# Schematic.net
KiCad netlist of a schematic drawn in EAGLE
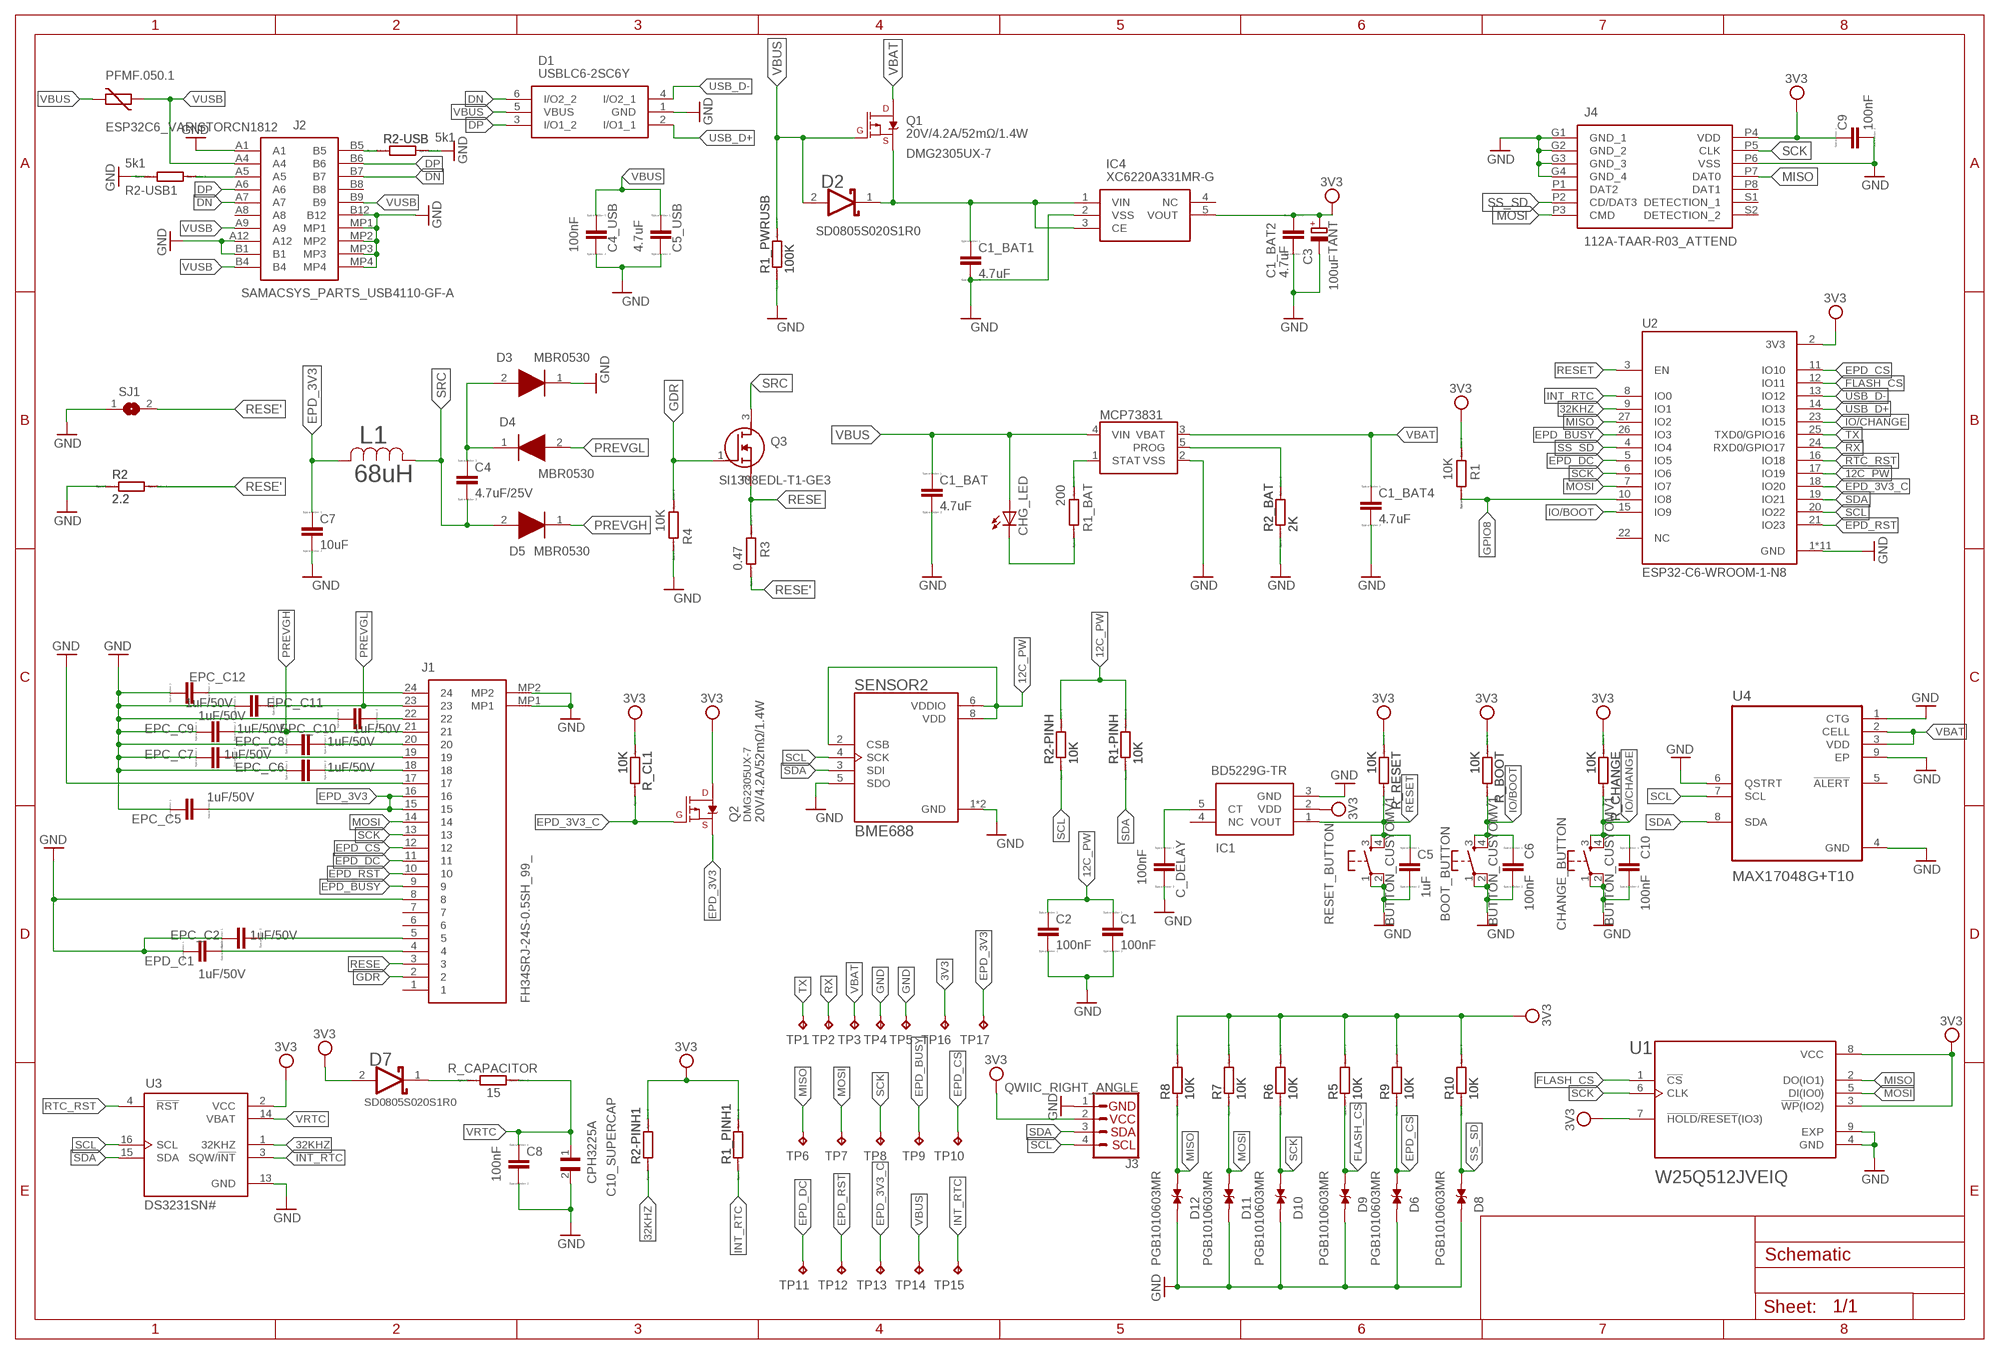
[diagram p0: schematic, sheet 1]

(export (version "E")
  (design (tool "Eeschema 10.0.6"))
  (components
    (comp (ref "BOOT_BUTTON")
      (value "BUTTON_CUSYOMV1")
      (footprint "eagle-import:MYBUTTON")
      (libsource (lib "eagle-import") (part "BUTTON_CUSYOMV1"))
    )
    (comp (ref "C1")
      (value "100nF")
      (footprint "eagle-import:EAGLE-LTSPICE_C0402")
      (libsource (lib "eagle-import") (part "EAGLE-LTSPICE_CC0402"))
    )
    (comp (ref "C1_BAT")
      (value "4.7uF")
      (footprint "eagle-import:EAGLE-LTSPICE_C0402")
      (libsource (lib "eagle-import") (part "EAGLE-LTSPICE_CC0402"))
    )
    (comp (ref "C1_BAT1")
      (value "4.7uF")
      (footprint "eagle-import:EAGLE-LTSPICE_C0402")
      (libsource (lib "eagle-import") (part "EAGLE-LTSPICE_CC0402"))
    )
    (comp (ref "C1_BAT2")
      (value "4.7uF")
      (footprint "eagle-import:EAGLE-LTSPICE_C0402")
      (libsource (lib "eagle-import") (part "EAGLE-LTSPICE_CC0402"))
    )
    (comp (ref "C1_BAT4")
      (value "4.7uF")
      (footprint "eagle-import:EAGLE-LTSPICE_C0402")
      (libsource (lib "eagle-import") (part "EAGLE-LTSPICE_CC0402"))
    )
    (comp (ref "C2")
      (value "100nF")
      (footprint "eagle-import:EAGLE-LTSPICE_C0402")
      (libsource (lib "eagle-import") (part "EAGLE-LTSPICE_CC0402"))
    )
    (comp (ref "C3")
      (value "100uF")
      (footprint "eagle-import:RCL_CT3528")
      (libsource (lib "eagle-import") (part "RCL_CPOL-EUCT3528"))
    )
    (comp (ref "C4")
      (value "4.7uF/25V")
      (footprint "eagle-import:EAGLE-LTSPICE_C0402")
      (libsource (lib "eagle-import") (part "EAGLE-LTSPICE_CC0402"))
    )
    (comp (ref "C4_USB")
      (value "100nF")
      (footprint "eagle-import:EAGLE-LTSPICE_C0402")
      (libsource (lib "eagle-import") (part "EAGLE-LTSPICE_CC0402"))
    )
    (comp (ref "C5")
      (value "1uF")
      (footprint "eagle-import:EAGLE-LTSPICE_C0402")
      (libsource (lib "eagle-import") (part "EAGLE-LTSPICE_CC0402"))
    )
    (comp (ref "C5_USB")
      (value "4.7uF")
      (footprint "eagle-import:EAGLE-LTSPICE_C0402")
      (libsource (lib "eagle-import") (part "EAGLE-LTSPICE_CC0402"))
    )
    (comp (ref "C6")
      (value "100nF")
      (footprint "eagle-import:EAGLE-LTSPICE_C0402")
      (libsource (lib "eagle-import") (part "EAGLE-LTSPICE_CC0402"))
    )
    (comp (ref "C7")
      (value "10uF")
      (footprint "eagle-import:EAGLE-LTSPICE_C0402")
      (libsource (lib "eagle-import") (part "EAGLE-LTSPICE_CC0402"))
    )
    (comp (ref "C8")
      (value "100nF")
      (footprint "eagle-import:EAGLE-LTSPICE_C0402")
      (libsource (lib "eagle-import") (part "EAGLE-LTSPICE_CC0402"))
    )
    (comp (ref "C9")
      (value "100nF")
      (footprint "eagle-import:EAGLE-LTSPICE_C0402")
      (libsource (lib "eagle-import") (part "EAGLE-LTSPICE_CC0402"))
    )
    (comp (ref "C10")
      (value "100nF")
      (footprint "eagle-import:EAGLE-LTSPICE_C0402")
      (libsource (lib "eagle-import") (part "EAGLE-LTSPICE_CC0402"))
    )
    (comp (ref "C10_SUPERCAP")
      (value "CPH3225A")
      (footprint "eagle-import:CAPCP3225X100N")
      (fields (field (name "MF") "Seiko Instruments"))
      (libsource (lib "eagle-import") (part "CPH3225A"))
    )
    (comp (ref "CHANGE_BUTTON")
      (value "BUTTON_CUSYOMV1")
      (footprint "eagle-import:MYBUTTON")
      (libsource (lib "eagle-import") (part "BUTTON_CUSYOMV1"))
    )
    (comp (ref "CHG_LED")
      (value "ADAFRUIT_LEDCHIP-LED0603")
      (footprint "eagle-import:ADAFRUIT_CHIP-LED0603")
      (libsource (lib "eagle-import") (part "ADAFRUIT_LEDCHIP-LED0603"))
    )
    (comp (ref "C_DELAY")
      (value "100nF")
      (footprint "eagle-import:EAGLE-LTSPICE_C0402")
      (libsource (lib "eagle-import") (part "EAGLE-LTSPICE_CC0402"))
    )
    (comp (ref "D1")
      (value "USBLC6-2SC6Y")
      (footprint "eagle-import:SOT95P280X145-6N")
      (fields (field (name "MF") "STMicroelectronics"))
      (libsource (lib "eagle-import") (part "USBLC6-2SC6Y"))
    )
    (comp (ref "D2")
      (value "ESP32_WROVER_AVX---SD0805S020S1R0_AVX_SD0805S020S1R0_0_0AVX_SD0805S020S1R0_0_0")
      (footprint "eagle-import:ESP32_WROVER_AVX---SD0805S020S1R0_AVX_SD0805S020S1R0_0")
      (fields
        (field (name "DIGIKEY_PART_NUMBER") "478-7800-1-ND")
        (field (name "MF") "AVX")
        (field (name "MOUSER_PART_NUMBER") "581-SD0805S020S1R0")
      )
      (libsource (lib "eagle-import") (part "ESP32_WROVER_AVX---SD0805S020S1R0_AVX_SD0805S020S1R0_0_0AVX_SD0805S020S1R0_0_0"))
    )
    (comp (ref "D3")
      (value "MBR0530")
      (footprint "eagle-import:SOD3716X135N")
      (fields (field (name "MF") "ON Semiconductor"))
      (libsource (lib "eagle-import") (part "MBR0530"))
    )
    (comp (ref "D4")
      (value "MBR0530")
      (footprint "eagle-import:SOD3716X135N")
      (fields (field (name "MF") "ON Semiconductor"))
      (libsource (lib "eagle-import") (part "MBR0530"))
    )
    (comp (ref "D5")
      (value "MBR0530")
      (footprint "eagle-import:SOD3716X135N")
      (fields (field (name "MF") "ON Semiconductor"))
      (libsource (lib "eagle-import") (part "MBR0530"))
    )
    (comp (ref "D6")
      (value "PGB1010603MR")
      (footprint "eagle-import:DIOC1608X36N")
      (fields (field (name "MF") "Littelfuse Inc."))
      (libsource (lib "eagle-import") (part "PGB1010603MR"))
    )
    (comp (ref "D7")
      (value "SD0805S020S1R0")
      (footprint "eagle-import:ESP32_WROVER_AVX---SD0805S020S1R0_AVX_SD0805S020S1R0_0")
      (fields
        (field (name "DIGIKEY_PART_NUMBER") "478-7800-1-ND")
        (field (name "MF") "AVX")
        (field (name "MOUSER_PART_NUMBER") "581-SD0805S020S1R0")
      )
      (libsource (lib "eagle-import") (part "ESP32_WROVER_AVX---SD0805S020S1R0_AVX_SD0805S020S1R0_0_0AVX_SD0805S020S1R0_0_0"))
    )
    (comp (ref "D8")
      (value "PGB1010603MR")
      (footprint "eagle-import:DIOC1608X36N")
      (fields (field (name "MF") "Littelfuse Inc."))
      (libsource (lib "eagle-import") (part "PGB1010603MR"))
    )
    (comp (ref "D9")
      (value "PGB1010603MR")
      (footprint "eagle-import:DIOC1608X36N")
      (fields (field (name "MF") "Littelfuse Inc."))
      (libsource (lib "eagle-import") (part "PGB1010603MR"))
    )
    (comp (ref "D10")
      (value "PGB1010603MR")
      (footprint "eagle-import:DIOC1608X36N")
      (fields (field (name "MF") "Littelfuse Inc."))
      (libsource (lib "eagle-import") (part "PGB1010603MR"))
    )
    (comp (ref "D11")
      (value "PGB1010603MR")
      (footprint "eagle-import:DIOC1608X36N")
      (fields (field (name "MF") "Littelfuse Inc."))
      (libsource (lib "eagle-import") (part "PGB1010603MR"))
    )
    (comp (ref "D12")
      (value "PGB1010603MR")
      (footprint "eagle-import:DIOC1608X36N")
      (fields (field (name "MF") "Littelfuse Inc."))
      (libsource (lib "eagle-import") (part "PGB1010603MR"))
    )
    (comp (ref "EPC_C2")
      (value "1uF/50V")
      (footprint "eagle-import:ESP32_WROVER_EAGLE-LTSPICE_C0402")
      (libsource (lib "eagle-import") (part "ESP32_WROVER_EAGLE-LTSPICE_CC0402"))
    )
    (comp (ref "EPC_C5")
      (value "1uF/50V")
      (footprint "eagle-import:ESP32_WROVER_EAGLE-LTSPICE_C0402")
      (libsource (lib "eagle-import") (part "ESP32_WROVER_EAGLE-LTSPICE_CC0402"))
    )
    (comp (ref "EPC_C6")
      (value "1uF/50V")
      (footprint "eagle-import:ESP32_WROVER_EAGLE-LTSPICE_C0402")
      (libsource (lib "eagle-import") (part "ESP32_WROVER_EAGLE-LTSPICE_CC0402"))
    )
    (comp (ref "EPC_C7")
      (value "1uF/50V")
      (footprint "eagle-import:ESP32_WROVER_EAGLE-LTSPICE_C0402")
      (libsource (lib "eagle-import") (part "ESP32_WROVER_EAGLE-LTSPICE_CC0402"))
    )
    (comp (ref "EPC_C8")
      (value "1uF/50V")
      (footprint "eagle-import:ESP32_WROVER_EAGLE-LTSPICE_C0402")
      (libsource (lib "eagle-import") (part "ESP32_WROVER_EAGLE-LTSPICE_CC0402"))
    )
    (comp (ref "EPC_C9")
      (value "1uF/50V")
      (footprint "eagle-import:ESP32_WROVER_EAGLE-LTSPICE_C0402")
      (libsource (lib "eagle-import") (part "ESP32_WROVER_EAGLE-LTSPICE_CC0402"))
    )
    (comp (ref "EPC_C10")
      (value "1uF/50V")
      (footprint "eagle-import:ESP32_WROVER_EAGLE-LTSPICE_C0402")
      (libsource (lib "eagle-import") (part "ESP32_WROVER_EAGLE-LTSPICE_CC0402"))
    )
    (comp (ref "EPC_C11")
      (value "1uF/50V")
      (footprint "eagle-import:ESP32_WROVER_EAGLE-LTSPICE_C0402")
      (libsource (lib "eagle-import") (part "ESP32_WROVER_EAGLE-LTSPICE_CC0402"))
    )
    (comp (ref "EPC_C12")
      (value "1uF/50V")
      (footprint "eagle-import:ESP32_WROVER_EAGLE-LTSPICE_C0402")
      (libsource (lib "eagle-import") (part "ESP32_WROVER_EAGLE-LTSPICE_CC0402"))
    )
    (comp (ref "EPD_C1")
      (value "1uF/50V")
      (footprint "eagle-import:ESP32_WROVER_EAGLE-LTSPICE_C0402")
      (libsource (lib "eagle-import") (part "ESP32_WROVER_EAGLE-LTSPICE_CC0402"))
    )
    (comp (ref "IC1")
      (value "BD5229G-TR")
      (footprint "eagle-import:SOT95P280X125-5N")
      (fields (field (name "MOUSER_PART_NUMBER") "755-BD5229G-TR"))
      (libsource (lib "eagle-import") (part "BD5229G-TR"))
    )
    (comp (ref "IC4")
      (value "XC6220A331MR-G")
      (footprint "eagle-import:SOT95P280X120-5N")
      (fields (field (name "MOUSER_PART_NUMBER") "865-XC6220A331MR-G"))
      (libsource (lib "eagle-import") (part "XC6220A331MR-G"))
    )
    (comp (ref "J1")
      (value "FH34SRJ-24S-0.5SH_99_")
      (footprint "eagle-import:FH34SRJ24S05SH99")
      (fields
        (field (name "MANUFACTURER_PART_NUMBER") "FH34SRJ-24S-0.5SH(99)")
        (field (name "MOUSER_PART_NUMBER") "798-FH34SRJ24S05SH99")
      )
      (libsource (lib "eagle-import") (part "FH34SRJ-24S-0.5SH_99_"))
    )
    (comp (ref "J2")
      (value "SAMACSYS_PARTS_USB4110-GF-A")
      (footprint "eagle-import:SAMACSYS_PARTS_USB4110GFA")
      (fields
        (field (name "MANUFACTURER_PART_NUMBER") "USB4110-GF-A")
        (field (name "MOUSER_PART_NUMBER") "640-USB4110-GF-A")
      )
      (libsource (lib "eagle-import") (part "SAMACSYS_PARTS_USB4110-GF-A"))
    )
    (comp (ref "J3")
      (value "QWIIC_RIGHT_ANGLE")
      (footprint "eagle-import:JST04_1MM_RA")
      (libsource (lib "eagle-import") (part "QWIIC_CONNECTORJS-1MM"))
    )
    (comp (ref "J4")
      (value "112A-TAAR-R03_ATTEND")
      (footprint "eagle-import:112ATAARR03ATTEND")
      (fields (field (name "MANUFACTURER_PART_NUMBER") "112A-TAAR-R03 ATTEND"))
      (libsource (lib "eagle-import") (part "112A-TAAR-R03_ATTEND"))
    )
    (comp (ref "L1")
      (value "68uH")
      (footprint "eagle-import:IND_4828-WE-TPC_WRE")
      (fields
        (field (name "MANUFACTURER_PART_NUMBER") "744043680")
        (field (name "COPYRIGHT") "Copyright (C) 2024 Ultra Librarian. All rights reserved.")
      )
      (libsource (lib "eagle-import") (part "744043680IND_4828-WE-TPC_WRE"))
    )
    (comp (ref "MCP73831")
      (value "ESP32_WROVER_SPARKFUN-IC-POWER_MCP73831")
      (footprint "eagle-import:ESP32_WROVER_SPARKFUN-IC-POWER_SOT23-5")
      (libsource (lib "eagle-import") (part "ESP32_WROVER_SPARKFUN-IC-POWER_MCP73831"))
    )
    (comp (ref "PFMF.050.1")
      (value "ESP32C6_VARISTORCN1812")
      (footprint "eagle-import:ESP32C6_VARISTOR_CT_CN1812")
      (libsource (lib "eagle-import") (part "ESP32C6_VARISTORCN1812"))
    )
    (comp (ref "Q1")
      (value "20V/4.2A/52mΩ/1.4W")
      (footprint "eagle-import:ESP32_WROVER_SPARKFUN-DISCRETESEMI_SOT23-3")
      (libsource (lib "eagle-import") (part "ESP32_WROVER_SPARKFUN-DISCRETESEMI_MOSFET_PCH-DMG2305UX-7"))
    )
    (comp (ref "Q2")
      (value "20V/4.2A/52mΩ/1.4W")
      (footprint "eagle-import:ESP32_WROVER_SPARKFUN-DISCRETESEMI_SOT23-3")
      (libsource (lib "eagle-import") (part "ESP32_WROVER_SPARKFUN-DISCRETESEMI_MOSFET_PCH-DMG2305UX-7"))
    )
    (comp (ref "Q3")
      (value "SI1308EDL-T1-GE3")
      (footprint "eagle-import:SOT65P210X110-3N")
      (fields (field (name "MF") "Vishay Siliconix"))
      (libsource (lib "eagle-import") (part "SI1308EDL-T1-GE3"))
    )
    (comp (ref "R1")
      (value "10K")
      (footprint "eagle-import:ESP32_WROVER_EAGLE-LTSPICE_R0402")
      (libsource (lib "eagle-import") (part "ESP32_WROVER_EAGLE-LTSPICE_RR0402"))
    )
    (comp (ref "R1-PINH")
      (value "10K")
      (footprint "eagle-import:ESP32_WROVER_EAGLE-LTSPICE_R0402")
      (libsource (lib "eagle-import") (part "ESP32_WROVER_EAGLE-LTSPICE_RR0402"))
    )
    (comp (ref "R1_BAT")
      (value "200")
      (footprint "eagle-import:ESP32_WROVER_EAGLE-LTSPICE_R0402")
      (libsource (lib "eagle-import") (part "ESP32_WROVER_EAGLE-LTSPICE_RR0402"))
    )
    (comp (ref "R1_PINH1")
      (value "ESP32_WROVER_EAGLE-LTSPICE_RR0402")
      (footprint "eagle-import:ESP32_WROVER_EAGLE-LTSPICE_R0402")
      (libsource (lib "eagle-import") (part "ESP32_WROVER_EAGLE-LTSPICE_RR0402"))
    )
    (comp (ref "R1_PWRUSB")
      (value "100K")
      (footprint "eagle-import:ESP32_WROVER_EAGLE-LTSPICE_R0402")
      (libsource (lib "eagle-import") (part "ESP32_WROVER_EAGLE-LTSPICE_RR0402"))
    )
    (comp (ref "R2")
      (value "2.2")
      (footprint "eagle-import:ESP32_WROVER_EAGLE-LTSPICE_R0402")
      (libsource (lib "eagle-import") (part "ESP32_WROVER_EAGLE-LTSPICE_RR0402"))
    )
    (comp (ref "R2-PINH")
      (value "10K")
      (footprint "eagle-import:ESP32_WROVER_EAGLE-LTSPICE_R0402")
      (libsource (lib "eagle-import") (part "ESP32_WROVER_EAGLE-LTSPICE_RR0402"))
    )
    (comp (ref "R2-PINH1")
      (value "ESP32_WROVER_EAGLE-LTSPICE_RR0402")
      (footprint "eagle-import:ESP32_WROVER_EAGLE-LTSPICE_R0402")
      (libsource (lib "eagle-import") (part "ESP32_WROVER_EAGLE-LTSPICE_RR0402"))
    )
    (comp (ref "R2-USB")
      (value "5k1")
      (footprint "eagle-import:ESP32_WROVER_EAGLE-LTSPICE_R0402")
      (libsource (lib "eagle-import") (part "ESP32_WROVER_EAGLE-LTSPICE_RR0402"))
    )
    (comp (ref "R2-USB1")
      (value "5k1")
      (footprint "eagle-import:ESP32_WROVER_EAGLE-LTSPICE_R0402")
      (libsource (lib "eagle-import") (part "ESP32_WROVER_EAGLE-LTSPICE_RR0402"))
    )
    (comp (ref "R2_BAT")
      (value "2K")
      (footprint "eagle-import:ESP32_WROVER_EAGLE-LTSPICE_R0402")
      (libsource (lib "eagle-import") (part "ESP32_WROVER_EAGLE-LTSPICE_RR0402"))
    )
    (comp (ref "R3")
      (value "0.47")
      (footprint "eagle-import:ESP32_WROVER_EAGLE-LTSPICE_R0402")
      (libsource (lib "eagle-import") (part "ESP32_WROVER_EAGLE-LTSPICE_RR0402"))
    )
    (comp (ref "R4")
      (value "10K")
      (footprint "eagle-import:ESP32_WROVER_EAGLE-LTSPICE_R0402")
      (libsource (lib "eagle-import") (part "ESP32_WROVER_EAGLE-LTSPICE_RR0402"))
    )
    (comp (ref "R5")
      (value "10K")
      (footprint "eagle-import:ESP32_WROVER_EAGLE-LTSPICE_R0402")
      (libsource (lib "eagle-import") (part "ESP32_WROVER_EAGLE-LTSPICE_RR0402"))
    )
    (comp (ref "R6")
      (value "10K")
      (footprint "eagle-import:ESP32_WROVER_EAGLE-LTSPICE_R0402")
      (libsource (lib "eagle-import") (part "ESP32_WROVER_EAGLE-LTSPICE_RR0402"))
    )
    (comp (ref "R7")
      (value "10K")
      (footprint "eagle-import:ESP32_WROVER_EAGLE-LTSPICE_R0402")
      (libsource (lib "eagle-import") (part "ESP32_WROVER_EAGLE-LTSPICE_RR0402"))
    )
    (comp (ref "R8")
      (value "10K")
      (footprint "eagle-import:ESP32_WROVER_EAGLE-LTSPICE_R0402")
      (libsource (lib "eagle-import") (part "ESP32_WROVER_EAGLE-LTSPICE_RR0402"))
    )
    (comp (ref "R9")
      (value "10K")
      (footprint "eagle-import:ESP32_WROVER_EAGLE-LTSPICE_R0402")
      (libsource (lib "eagle-import") (part "ESP32_WROVER_EAGLE-LTSPICE_RR0402"))
    )
    (comp (ref "R10")
      (value "10K")
      (footprint "eagle-import:ESP32_WROVER_EAGLE-LTSPICE_R0402")
      (libsource (lib "eagle-import") (part "ESP32_WROVER_EAGLE-LTSPICE_RR0402"))
    )
    (comp (ref "RESET_BUTTON")
      (value "BUTTON_CUSYOMV1")
      (footprint "eagle-import:MYBUTTON")
      (libsource (lib "eagle-import") (part "BUTTON_CUSYOMV1"))
    )
    (comp (ref "R_BOOT")
      (value "10K")
      (footprint "eagle-import:ESP32_WROVER_EAGLE-LTSPICE_R0402")
      (libsource (lib "eagle-import") (part "ESP32_WROVER_EAGLE-LTSPICE_RR0402"))
    )
    (comp (ref "R_CAPACITOR")
      (value "15")
      (footprint "eagle-import:ESP32_WROVER_EAGLE-LTSPICE_R0402")
      (libsource (lib "eagle-import") (part "ESP32_WROVER_EAGLE-LTSPICE_RR0402"))
    )
    (comp (ref "R_CHANGE")
      (value "10K")
      (footprint "eagle-import:ESP32_WROVER_EAGLE-LTSPICE_R0402")
      (libsource (lib "eagle-import") (part "ESP32_WROVER_EAGLE-LTSPICE_RR0402"))
    )
    (comp (ref "R_CL1")
      (value "10K")
      (footprint "eagle-import:ESP32_WROVER_EAGLE-LTSPICE_R0402")
      (libsource (lib "eagle-import") (part "ESP32_WROVER_EAGLE-LTSPICE_RR0402"))
    )
    (comp (ref "R_RESET")
      (value "10K")
      (footprint "eagle-import:ESP32_WROVER_EAGLE-LTSPICE_R0402")
      (libsource (lib "eagle-import") (part "ESP32_WROVER_EAGLE-LTSPICE_RR0402"))
    )
    (comp (ref "SENSOR2")
      (value "BME688")
      (footprint "eagle-import:ESP32_WROVER_BME680_PSON80P300X300X100-8N")
      (fields (field (name "MF") "Bosch Sensortec") (field (name "MP") "BME680"))
      (libsource (lib "eagle-import") (part "ESP32_WROVER_BME680_BME680"))
    )
    (comp (ref "SJ1") (value "SJ") (footprint "eagle-import:SJ") (libsource (lib "eagle-import") (part "SJ")))
    (comp (ref "TP1")
      (value "TPTP20R")
      (footprint "eagle-import:TP20R")
      (libsource (lib "eagle-import") (part "TPTP20R"))
    )
    (comp (ref "TP2")
      (value "TPTP20R")
      (footprint "eagle-import:TP20R")
      (libsource (lib "eagle-import") (part "TPTP20R"))
    )
    (comp (ref "TP3")
      (value "TPTP20R")
      (footprint "eagle-import:TP20R")
      (libsource (lib "eagle-import") (part "TPTP20R"))
    )
    (comp (ref "TP4")
      (value "TPTP20R")
      (footprint "eagle-import:TP20R")
      (libsource (lib "eagle-import") (part "TPTP20R"))
    )
    (comp (ref "TP5")
      (value "TPTP20R")
      (footprint "eagle-import:TP20R")
      (libsource (lib "eagle-import") (part "TPTP20R"))
    )
    (comp (ref "TP6")
      (value "TPTP20R")
      (footprint "eagle-import:TP20R")
      (libsource (lib "eagle-import") (part "TPTP20R"))
    )
    (comp (ref "TP7")
      (value "TPTP20R")
      (footprint "eagle-import:TP20R")
      (libsource (lib "eagle-import") (part "TPTP20R"))
    )
    (comp (ref "TP8")
      (value "TPTP20R")
      (footprint "eagle-import:TP20R")
      (libsource (lib "eagle-import") (part "TPTP20R"))
    )
    (comp (ref "TP9")
      (value "TPTP20R")
      (footprint "eagle-import:TP20R")
      (libsource (lib "eagle-import") (part "TPTP20R"))
    )
    (comp (ref "TP10")
      (value "TPTP20R")
      (footprint "eagle-import:TP20R")
      (libsource (lib "eagle-import") (part "TPTP20R"))
    )
    (comp (ref "TP11")
      (value "TPTP20R")
      (footprint "eagle-import:TP20R")
      (libsource (lib "eagle-import") (part "TPTP20R"))
    )
    (comp (ref "TP12")
      (value "TPTP20R")
      (footprint "eagle-import:TP20R")
      (libsource (lib "eagle-import") (part "TPTP20R"))
    )
    (comp (ref "TP13")
      (value "TPTP20R")
      (footprint "eagle-import:TP20R")
      (libsource (lib "eagle-import") (part "TPTP20R"))
    )
    (comp (ref "TP14")
      (value "TPTP20R")
      (footprint "eagle-import:TP20R")
      (libsource (lib "eagle-import") (part "TPTP20R"))
    )
    (comp (ref "TP15")
      (value "TPTP20R")
      (footprint "eagle-import:TP20R")
      (libsource (lib "eagle-import") (part "TPTP20R"))
    )
    (comp (ref "TP16")
      (value "TPTP20R")
      (footprint "eagle-import:TP20R")
      (libsource (lib "eagle-import") (part "TPTP20R"))
    )
    (comp (ref "TP17")
      (value "TPTP20R")
      (footprint "eagle-import:TP20R")
      (libsource (lib "eagle-import") (part "TPTP20R"))
    )
    (comp (ref "U1")
      (value "W25Q512JVEIQ")
      (footprint "eagle-import:SON127P600X800X80-9N")
      (fields (field (name "MF") "Winbond Electronics"))
      (libsource (lib "eagle-import") (part "W25Q512JVEIQ"))
    )
    (comp (ref "U2")
      (value "ESP32-C6-WROOM-1-N8")
      (footprint "eagle-import:XCVR_ESP32-C6-WROOM-1-N8")
      (fields (field (name "MF") "Espressif Systems"))
      (libsource (lib "eagle-import") (part "ESP32-C6-WROOM-1-N8"))
    )
    (comp (ref "U3")
      (value "DS3231SN#")
      (footprint "eagle-import:SOIC127P1032X265-16N")
      (fields (field (name "MF") "Analog Devices"))
      (libsource (lib "eagle-import") (part "DS3231SN#"))
    )
    (comp (ref "U4")
      (value "MAX17048G+T10")
      (footprint "eagle-import:SON50P200X200X80-9N")
      (fields (field (name "MF") "Analog Devices"))
      (libsource (lib "eagle-import") (part "MAX17048G+T10"))
    )
  )
  (nets
    (net (code "1") (name "3V3") (class "Default")
      (node (ref "C1_BAT2") (pin "1") (pinfunction "1_1") (pintype "passive"))
      (node (ref "C3") (pin "+") (pinfunction "+_+") (pintype "passive"))
      (node (ref "C9") (pin "1") (pinfunction "1_1") (pintype "passive"))
      (node (ref "D7") (pin "2") (pinfunction "ANODE_2") (pintype "bidirectional"))
      (node (ref "IC1") (pin "2") (pinfunction "VDD_2") (pintype "bidirectional"))
      (node (ref "IC4") (pin "5") (pinfunction "VOUT_5") (pintype "bidirectional"))
      (node (ref "J3") (pin "2") (pinfunction "2_2") (pintype "power_in"))
      (node (ref "J4") (pin "P4") (pinfunction "VDD_P4") (pintype "bidirectional"))
      (node (ref "Q2") (pin "3") (pinfunction "D_3") (pintype "bidirectional"))
      (node (ref "R1") (pin "2") (pinfunction "2_2") (pintype "passive"))
      (node (ref "R10") (pin "2") (pinfunction "2_2") (pintype "passive"))
      (node (ref "R1_PINH1") (pin "2") (pinfunction "2_2") (pintype "passive"))
      (node (ref "R2-PINH1") (pin "2") (pinfunction "2_2") (pintype "passive"))
      (node (ref "R5") (pin "2") (pinfunction "2_2") (pintype "passive"))
      (node (ref "R6") (pin "2") (pinfunction "2_2") (pintype "passive"))
      (node (ref "R7") (pin "2") (pinfunction "2_2") (pintype "passive"))
      (node (ref "R8") (pin "2") (pinfunction "2_2") (pintype "passive"))
      (node (ref "R9") (pin "2") (pinfunction "2_2") (pintype "passive"))
      (node (ref "R_BOOT") (pin "1") (pinfunction "1_1") (pintype "passive"))
      (node (ref "R_CHANGE") (pin "1") (pinfunction "1_1") (pintype "passive"))
      (node (ref "R_CL1") (pin "1") (pinfunction "1_1") (pintype "passive"))
      (node (ref "R_RESET") (pin "1") (pinfunction "1_1") (pintype "passive"))
      (node (ref "TP16") (pin "TP") (pinfunction "TP_TP") (pintype "input"))
      (node (ref "U1") (pin "3") (pinfunction "~{WP}(IO2)_3") (pintype "bidirectional"))
      (node (ref "U1") (pin "7") (pinfunction "~{HOLD}/~{RESET}(IO3)_7") (pintype "bidirectional"))
      (node (ref "U1") (pin "8") (pinfunction "VCC_8") (pintype "power_in"))
      (node (ref "U2") (pin "2") (pinfunction "3V3_2") (pintype "power_in"))
      (node (ref "U3") (pin "2") (pinfunction "VCC_2") (pintype "power_in"))
    )
    (net (code "2") (name "12C_PW") (class "Default")
      (node (ref "C1") (pin "1") (pinfunction "1_1") (pintype "passive"))
      (node (ref "C2") (pin "1") (pinfunction "1_1") (pintype "passive"))
      (node (ref "R1-PINH") (pin "2") (pinfunction "2_2") (pintype "passive"))
      (node (ref "R2-PINH") (pin "2") (pinfunction "2_2") (pintype "passive"))
      (node (ref "SENSOR2") (pin "2") (pinfunction "CSB_2") (pintype "input"))
      (node (ref "SENSOR2") (pin "6") (pinfunction "VDDIO_6") (pintype "power_in"))
      (node (ref "SENSOR2") (pin "8") (pinfunction "VDD_8") (pintype "power_in"))
      (node (ref "U2") (pin "17") (pinfunction "IO19_17") (pintype "bidirectional"))
    )
    (net (code "3") (name "32KHZ") (class "Default")
      (node (ref "R2-PINH1") (pin "1") (pinfunction "1_1") (pintype "passive"))
      (node (ref "U2") (pin "9") (pinfunction "IO1_9") (pintype "bidirectional"))
      (node (ref "U3") (pin "1") (pinfunction "32KHZ_1") (pintype "output"))
    )
    (net (code "4") (name "DN") (class "Default")
      (node (ref "D1") (pin "6") (pinfunction "I/O2_2_6") (pintype "bidirectional"))
      (node (ref "J2") (pin "A7") (pinfunction "A7_A7") (pintype "bidirectional"))
      (node (ref "J2") (pin "B7") (pinfunction "B7_B7") (pintype "bidirectional"))
    )
    (net (code "5") (name "DP") (class "Default")
      (node (ref "D1") (pin "3") (pinfunction "I/O1_2_3") (pintype "bidirectional"))
      (node (ref "J2") (pin "A6") (pinfunction "A6_A6") (pintype "bidirectional"))
      (node (ref "J2") (pin "B6") (pinfunction "B6_B6") (pintype "bidirectional"))
    )
    (net (code "6") (name "EPD_3V3") (class "Default")
      (node (ref "C7") (pin "1") (pinfunction "1_1") (pintype "passive"))
      (node (ref "EPC_C5") (pin "2") (pinfunction "2_2") (pintype "passive"))
      (node (ref "J1") (pin "15") (pinfunction "15_15") (pintype "bidirectional"))
      (node (ref "J1") (pin "16") (pinfunction "16_16") (pintype "bidirectional"))
      (node (ref "L1") (pin "2") (pinfunction "2_2") (pintype "passive"))
      (node (ref "Q2") (pin "2") (pinfunction "S_2") (pintype "bidirectional"))
      (node (ref "TP17") (pin "TP") (pinfunction "TP_TP") (pintype "input"))
    )
    (net (code "7") (name "EPD_3V3_C") (class "Default")
      (node (ref "Q2") (pin "1") (pinfunction "G_1") (pintype "bidirectional"))
      (node (ref "R_CL1") (pin "2") (pinfunction "2_2") (pintype "passive"))
      (node (ref "TP13") (pin "TP") (pinfunction "TP_TP") (pintype "input"))
      (node (ref "U2") (pin "18") (pinfunction "IO20_18") (pintype "bidirectional"))
    )
    (net (code "8") (name "EPD_BUSY") (class "Default")
      (node (ref "J1") (pin "9") (pinfunction "9_9") (pintype "bidirectional"))
      (node (ref "TP9") (pin "TP") (pinfunction "TP_TP") (pintype "input"))
      (node (ref "U2") (pin "26") (pinfunction "IO3_26") (pintype "bidirectional"))
    )
    (net (code "9") (name "EPD_CS") (class "Default")
      (node (ref "D6") (pin "1") (pinfunction "1_1") (pintype "passive"))
      (node (ref "J1") (pin "12") (pinfunction "12_12") (pintype "bidirectional"))
      (node (ref "R9") (pin "1") (pinfunction "1_1") (pintype "passive"))
      (node (ref "TP10") (pin "TP") (pinfunction "TP_TP") (pintype "input"))
      (node (ref "U2") (pin "11") (pinfunction "IO10_11") (pintype "bidirectional"))
    )
    (net (code "10") (name "EPD_DC") (class "Default")
      (node (ref "J1") (pin "11") (pinfunction "11_11") (pintype "bidirectional"))
      (node (ref "TP11") (pin "TP") (pinfunction "TP_TP") (pintype "input"))
      (node (ref "U2") (pin "5") (pinfunction "IO5_5") (pintype "bidirectional"))
    )
    (net (code "11") (name "EPD_RST") (class "Default")
      (node (ref "J1") (pin "10") (pinfunction "10_10") (pintype "bidirectional"))
      (node (ref "TP12") (pin "TP") (pinfunction "TP_TP") (pintype "input"))
      (node (ref "U2") (pin "21") (pinfunction "IO23_21") (pintype "bidirectional"))
    )
    (net (code "12") (name "FLASH_CS") (class "Default")
      (node (ref "D9") (pin "1") (pinfunction "1_1") (pintype "passive"))
      (node (ref "R5") (pin "1") (pinfunction "1_1") (pintype "passive"))
      (node (ref "U1") (pin "1") (pinfunction "~{CS}_1") (pintype "input"))
      (node (ref "U2") (pin "12") (pinfunction "IO11_12") (pintype "bidirectional"))
    )
    (net (code "13") (name "GDR") (class "Default")
      (node (ref "J1") (pin "2") (pinfunction "2_2") (pintype "bidirectional"))
      (node (ref "Q3") (pin "1") (pinfunction "G_1") (pintype "bidirectional"))
      (node (ref "R4") (pin "2") (pinfunction "2_2") (pintype "passive"))
    )
    (net (code "14") (name "GND") (class "Default")
      (node (ref "BOOT_BUTTON") (pin "1") (pinfunction "1_1") (pintype "passive"))
      (node (ref "BOOT_BUTTON") (pin "2") (pinfunction "2_2") (pintype "passive"))
      (node (ref "C1") (pin "2") (pinfunction "2_2") (pintype "passive"))
      (node (ref "C10") (pin "2") (pinfunction "2_2") (pintype "passive"))
      (node (ref "C10_SUPERCAP") (pin "2") (pinfunction "2_2") (pintype "passive"))
      (node (ref "C1_BAT") (pin "2") (pinfunction "2_2") (pintype "passive"))
      (node (ref "C1_BAT1") (pin "2") (pinfunction "2_2") (pintype "passive"))
      (node (ref "C1_BAT2") (pin "2") (pinfunction "2_2") (pintype "passive"))
      (node (ref "C1_BAT4") (pin "2") (pinfunction "2_2") (pintype "passive"))
      (node (ref "C2") (pin "2") (pinfunction "2_2") (pintype "passive"))
      (node (ref "C3") (pin "-") (pinfunction "-_-") (pintype "passive"))
      (node (ref "C4_USB") (pin "2") (pinfunction "2_2") (pintype "passive"))
      (node (ref "C5") (pin "2") (pinfunction "2_2") (pintype "passive"))
      (node (ref "C5_USB") (pin "2") (pinfunction "2_2") (pintype "passive"))
      (node (ref "C6") (pin "2") (pinfunction "2_2") (pintype "passive"))
      (node (ref "C7") (pin "2") (pinfunction "2_2") (pintype "passive"))
      (node (ref "C8") (pin "2") (pinfunction "2_2") (pintype "passive"))
      (node (ref "C9") (pin "2") (pinfunction "2_2") (pintype "passive"))
      (node (ref "CHANGE_BUTTON") (pin "1") (pinfunction "1_1") (pintype "passive"))
      (node (ref "CHANGE_BUTTON") (pin "2") (pinfunction "2_2") (pintype "passive"))
      (node (ref "C_DELAY") (pin "2") (pinfunction "2_2") (pintype "passive"))
      (node (ref "D1") (pin "1") (pinfunction "GND_1") (pintype "bidirectional"))
      (node (ref "D10") (pin "2") (pinfunction "2_2") (pintype "passive"))
      (node (ref "D11") (pin "2") (pinfunction "2_2") (pintype "passive"))
      (node (ref "D12") (pin "2") (pinfunction "2_2") (pintype "passive"))
      (node (ref "D3") (pin "1") (pinfunction "K_1") (pintype "bidirectional"))
      (node (ref "D6") (pin "2") (pinfunction "2_2") (pintype "passive"))
      (node (ref "D8") (pin "2") (pinfunction "2_2") (pintype "passive"))
      (node (ref "D9") (pin "2") (pinfunction "2_2") (pintype "passive"))
      (node (ref "EPC_C10") (pin "1") (pinfunction "1_1") (pintype "passive"))
      (node (ref "EPC_C11") (pin "1") (pinfunction "1_1") (pintype "passive"))
      (node (ref "EPC_C12") (pin "1") (pinfunction "1_1") (pintype "passive"))
      (node (ref "EPC_C2") (pin "1") (pinfunction "1_1") (pintype "passive"))
      (node (ref "EPC_C5") (pin "1") (pinfunction "1_1") (pintype "passive"))
      (node (ref "EPC_C6") (pin "1") (pinfunction "1_1") (pintype "passive"))
      (node (ref "EPC_C7") (pin "1") (pinfunction "1_1") (pintype "passive"))
      (node (ref "EPC_C8") (pin "1") (pinfunction "1_1") (pintype "passive"))
      (node (ref "EPC_C9") (pin "1") (pinfunction "1_1") (pintype "passive"))
      (node (ref "EPD_C1") (pin "1") (pinfunction "1_1") (pintype "passive"))
      (node (ref "IC1") (pin "3") (pinfunction "GND_3") (pintype "bidirectional"))
      (node (ref "IC4") (pin "2") (pinfunction "VSS_2") (pintype "bidirectional"))
      (node (ref "J1") (pin "17") (pinfunction "17_17") (pintype "bidirectional"))
      (node (ref "J1") (pin "8") (pinfunction "8_8") (pintype "bidirectional"))
      (node (ref "J1") (pin "MP1") (pinfunction "MP1_MP1") (pintype "bidirectional"))
      (node (ref "J1") (pin "MP2") (pinfunction "MP2_MP2") (pintype "bidirectional"))
      (node (ref "J2") (pin "A1") (pinfunction "A1_A1") (pintype "bidirectional"))
      (node (ref "J2") (pin "A12") (pinfunction "A12_A12") (pintype "bidirectional"))
      (node (ref "J2") (pin "B1") (pinfunction "B1_B1") (pintype "bidirectional"))
      (node (ref "J2") (pin "B12") (pinfunction "B12_B12") (pintype "bidirectional"))
      (node (ref "J2") (pin "MP1") (pinfunction "MP1_MP1") (pintype "bidirectional"))
      (node (ref "J2") (pin "MP2") (pinfunction "MP2_MP2") (pintype "bidirectional"))
      (node (ref "J2") (pin "MP3") (pinfunction "MP3_MP3") (pintype "bidirectional"))
      (node (ref "J2") (pin "MP4") (pinfunction "MP4_MP4") (pintype "bidirectional"))
      (node (ref "J3") (pin "1") (pinfunction "1_1") (pintype "power_in"))
      (node (ref "J4") (pin "G1") (pinfunction "GND_1_G1") (pintype "bidirectional"))
      (node (ref "J4") (pin "G2") (pinfunction "GND_2_G2") (pintype "bidirectional"))
      (node (ref "J4") (pin "G3") (pinfunction "GND_3_G3") (pintype "bidirectional"))
      (node (ref "J4") (pin "G4") (pinfunction "GND_4_G4") (pintype "bidirectional"))
      (node (ref "J4") (pin "P6") (pinfunction "VSS_P6") (pintype "bidirectional"))
      (node (ref "MCP73831") (pin "2") (pinfunction "VSS_2") (pintype "power_in"))
      (node (ref "R1_PWRUSB") (pin "1") (pinfunction "1_1") (pintype "passive"))
      (node (ref "R2") (pin "1") (pinfunction "1_1") (pintype "passive"))
      (node (ref "R2-USB") (pin "2") (pinfunction "2_2") (pintype "passive"))
      (node (ref "R2-USB1") (pin "1") (pinfunction "1_1") (pintype "passive"))
      (node (ref "R2_BAT") (pin "1") (pinfunction "1_1") (pintype "passive"))
      (node (ref "R4") (pin "1") (pinfunction "1_1") (pintype "passive"))
      (node (ref "RESET_BUTTON") (pin "1") (pinfunction "1_1") (pintype "passive"))
      (node (ref "RESET_BUTTON") (pin "2") (pinfunction "2_2") (pintype "passive"))
      (node (ref "SENSOR2") (pin "1") (pinfunction "GND_1") (pintype "power_in"))
      (node (ref "SENSOR2") (pin "5") (pinfunction "SDO_5") (pintype "bidirectional"))
      (node (ref "SENSOR2") (pin "7") (pinfunction "GND_7") (pintype "power_in"))
      (node (ref "SJ1") (pin "1") (pinfunction "1_1") (pintype "passive"))
      (node (ref "TP4") (pin "TP") (pinfunction "TP_TP") (pintype "input"))
      (node (ref "TP5") (pin "TP") (pinfunction "TP_TP") (pintype "input"))
      (node (ref "U1") (pin "4") (pinfunction "GND_4") (pintype "power_in"))
      (node (ref "U1") (pin "9") (pinfunction "EXP_9") (pintype "passive"))
      (node (ref "U2") (pin "1") (pinfunction "GND_1") (pintype "power_in"))
      (node (ref "U2") (pin "28") (pinfunction "GND_28") (pintype "power_in"))
      (node (ref "U2") (pin "29_1") (pinfunction "GND_29_1") (pintype "power_in"))
      (node (ref "U2") (pin "29_2") (pinfunction "GND_29_2") (pintype "power_in"))
      (node (ref "U2") (pin "29_3") (pinfunction "GND_29_3") (pintype "power_in"))
      (node (ref "U2") (pin "29_4") (pinfunction "GND_29_4") (pintype "power_in"))
      (node (ref "U2") (pin "29_5") (pinfunction "GND_29_5") (pintype "power_in"))
      (node (ref "U2") (pin "29_6") (pinfunction "GND_29_6") (pintype "power_in"))
      (node (ref "U2") (pin "29_7") (pinfunction "GND_29_7") (pintype "power_in"))
      (node (ref "U2") (pin "29_8") (pinfunction "GND_29_8") (pintype "power_in"))
      (node (ref "U2") (pin "29_9") (pinfunction "GND_29_9") (pintype "power_in"))
      (node (ref "U3") (pin "13") (pinfunction "GND_13") (pintype "power_in"))
      (node (ref "U4") (pin "1") (pinfunction "CTG_1") (pintype "power_in"))
      (node (ref "U4") (pin "4") (pinfunction "GND_4") (pintype "power_in"))
      (node (ref "U4") (pin "6") (pinfunction "QSTRT_6") (pintype "input"))
      (node (ref "U4") (pin "9") (pinfunction "EP_9") (pintype "power_in"))
    )
    (net (code "15") (name "GPIO8") (class "Default")
      (node (ref "R1") (pin "1") (pinfunction "1_1") (pintype "passive"))
      (node (ref "U2") (pin "10") (pinfunction "IO8_10") (pintype "bidirectional"))
    )
    (net (code "16") (name "INT_RTC") (class "Default")
      (node (ref "R1_PINH1") (pin "1") (pinfunction "1_1") (pintype "passive"))
      (node (ref "TP15") (pin "TP") (pinfunction "TP_TP") (pintype "input"))
      (node (ref "U2") (pin "8") (pinfunction "IO0_8") (pintype "bidirectional"))
      (node (ref "U3") (pin "3") (pinfunction "SQW/~{INT}_3") (pintype "output"))
    )
    (net (code "17") (name "IO{slash}BOOT") (class "Default")
      (node (ref "BOOT_BUTTON") (pin "3") (pinfunction "3_3") (pintype "passive"))
      (node (ref "BOOT_BUTTON") (pin "4") (pinfunction "4_4") (pintype "passive"))
      (node (ref "C6") (pin "1") (pinfunction "1_1") (pintype "passive"))
      (node (ref "R_BOOT") (pin "2") (pinfunction "2_2") (pintype "passive"))
      (node (ref "U2") (pin "15") (pinfunction "IO9_15") (pintype "bidirectional"))
    )
    (net (code "18") (name "IO{slash}CHANGE") (class "Default")
      (node (ref "C10") (pin "1") (pinfunction "1_1") (pintype "passive"))
      (node (ref "CHANGE_BUTTON") (pin "3") (pinfunction "3_3") (pintype "passive"))
      (node (ref "CHANGE_BUTTON") (pin "4") (pinfunction "4_4") (pintype "passive"))
      (node (ref "R_CHANGE") (pin "2") (pinfunction "2_2") (pintype "passive"))
      (node (ref "U2") (pin "23") (pinfunction "IO15_23") (pintype "bidirectional"))
    )
    (net (code "19") (name "MISO") (class "Default")
      (node (ref "D12") (pin "1") (pinfunction "1_1") (pintype "passive"))
      (node (ref "J4") (pin "P7") (pinfunction "DAT0_P7") (pintype "bidirectional"))
      (node (ref "R8") (pin "1") (pinfunction "1_1") (pintype "passive"))
      (node (ref "TP6") (pin "TP") (pinfunction "TP_TP") (pintype "input"))
      (node (ref "U1") (pin "2") (pinfunction "DO(IO1)_2") (pintype "bidirectional"))
      (node (ref "U2") (pin "27") (pinfunction "IO2_27") (pintype "bidirectional"))
    )
    (net (code "20") (name "MOSI") (class "Default")
      (node (ref "D11") (pin "1") (pinfunction "1_1") (pintype "passive"))
      (node (ref "J1") (pin "14") (pinfunction "14_14") (pintype "bidirectional"))
      (node (ref "J4") (pin "P3") (pinfunction "CMD_P3") (pintype "bidirectional"))
      (node (ref "R7") (pin "1") (pinfunction "1_1") (pintype "passive"))
      (node (ref "TP7") (pin "TP") (pinfunction "TP_TP") (pintype "input"))
      (node (ref "U1") (pin "5") (pinfunction "DI(IO0)_5") (pintype "bidirectional"))
      (node (ref "U2") (pin "7") (pinfunction "IO7_7") (pintype "bidirectional"))
    )
    (net (code "21") (name "Net-(CHG_LED-PadC)") (class "Default")
      (node (ref "CHG_LED") (pin "C") (pinfunction "C_C") (pintype "passive"))
      (node (ref "R1_BAT") (pin "1") (pinfunction "1_1") (pintype "passive"))
    )
    (net (code "22") (name "Net-(D2-CATHODE)") (class "Default")
      (node (ref "C1_BAT1") (pin "1") (pinfunction "1_1") (pintype "passive"))
      (node (ref "D2") (pin "1") (pinfunction "CATHODE_1") (pintype "bidirectional"))
      (node (ref "IC4") (pin "1") (pinfunction "VIN_1") (pintype "bidirectional"))
      (node (ref "IC4") (pin "3") (pinfunction "CE_3") (pintype "bidirectional"))
      (node (ref "Q1") (pin "2") (pinfunction "S_2") (pintype "bidirectional"))
    )
    (net (code "23") (name "Net-(D3-A)") (class "Default")
      (node (ref "C4") (pin "1") (pinfunction "1_1") (pintype "passive"))
      (node (ref "D3") (pin "2") (pinfunction "A_2") (pintype "bidirectional"))
      (node (ref "D4") (pin "1") (pinfunction "K_1") (pintype "bidirectional"))
    )
    (net (code "24") (name "Net-(D7-CATHODE)") (class "Default")
      (node (ref "D7") (pin "1") (pinfunction "CATHODE_1") (pintype "bidirectional"))
      (node (ref "R_CAPACITOR") (pin "1") (pinfunction "1_1") (pintype "passive"))
    )
    (net (code "25") (name "Net-(EPC_C2-Pad2)") (class "Default")
      (node (ref "EPC_C2") (pin "2") (pinfunction "2_2") (pintype "passive"))
      (node (ref "J1") (pin "5") (pinfunction "5_5") (pintype "bidirectional"))
    )
    (net (code "26") (name "Net-(EPC_C6-Pad2)") (class "Default")
      (node (ref "EPC_C6") (pin "2") (pinfunction "2_2") (pintype "passive"))
      (node (ref "J1") (pin "18") (pinfunction "18_18") (pintype "bidirectional"))
    )
    (net (code "27") (name "Net-(EPC_C7-Pad2)") (class "Default")
      (node (ref "EPC_C7") (pin "2") (pinfunction "2_2") (pintype "passive"))
      (node (ref "J1") (pin "19") (pinfunction "19_19") (pintype "bidirectional"))
    )
    (net (code "28") (name "Net-(EPC_C8-Pad2)") (class "Default")
      (node (ref "EPC_C8") (pin "2") (pinfunction "2_2") (pintype "passive"))
      (node (ref "J1") (pin "20") (pinfunction "20_20") (pintype "bidirectional"))
    )
    (net (code "29") (name "Net-(EPC_C10-Pad2)") (class "Default")
      (node (ref "EPC_C10") (pin "2") (pinfunction "2_2") (pintype "passive"))
      (node (ref "J1") (pin "22") (pinfunction "22_22") (pintype "bidirectional"))
    )
    (net (code "30") (name "Net-(EPC_C12-Pad2)") (class "Default")
      (node (ref "EPC_C12") (pin "2") (pinfunction "2_2") (pintype "passive"))
      (node (ref "J1") (pin "24") (pinfunction "24_24") (pintype "bidirectional"))
    )
    (net (code "31") (name "Net-(EPD_C1-Pad2)") (class "Default")
      (node (ref "EPD_C1") (pin "2") (pinfunction "2_2") (pintype "passive"))
      (node (ref "J1") (pin "4") (pinfunction "4_4") (pintype "bidirectional"))
    )
    (net (code "32") (name "Net-(IC1-CT)") (class "Default")
      (node (ref "C_DELAY") (pin "1") (pinfunction "1_1") (pintype "passive"))
      (node (ref "IC1") (pin "5") (pinfunction "CT_5") (pintype "bidirectional"))
    )
    (net (code "33") (name "Net-(J2-PadA5)") (class "Default")
      (node (ref "J2") (pin "A5") (pinfunction "A5_A5") (pintype "bidirectional"))
      (node (ref "R2-USB1") (pin "2") (pinfunction "2_2") (pintype "passive"))
    )
    (net (code "34") (name "Net-(J2-PadB5)") (class "Default")
      (node (ref "J2") (pin "B5") (pinfunction "B5_B5") (pintype "bidirectional"))
      (node (ref "R2-USB") (pin "1") (pinfunction "1_1") (pintype "passive"))
    )
    (net (code "35") (name "Net-(MCP73831-PROG)") (class "Default")
      (node (ref "MCP73831") (pin "5") (pinfunction "PROG_5") (pintype "input"))
      (node (ref "R2_BAT") (pin "2") (pinfunction "2_2") (pintype "passive"))
    )
    (net (code "36") (name "Net-(MCP73831-STAT)") (class "Default")
      (node (ref "MCP73831") (pin "1") (pinfunction "STAT_1") (pintype "output"))
      (node (ref "R1_BAT") (pin "2") (pinfunction "2_2") (pintype "passive"))
    )
    (net (code "37") (name "PREVGH") (class "Default")
      (node (ref "D5") (pin "1") (pinfunction "K_1") (pintype "bidirectional"))
      (node (ref "EPC_C9") (pin "2") (pinfunction "2_2") (pintype "passive"))
      (node (ref "J1") (pin "21") (pinfunction "21_21") (pintype "bidirectional"))
    )
    (net (code "38") (name "PREVGL") (class "Default")
      (node (ref "D4") (pin "2") (pinfunction "A_2") (pintype "bidirectional"))
      (node (ref "EPC_C11") (pin "2") (pinfunction "2_2") (pintype "passive"))
      (node (ref "J1") (pin "23") (pinfunction "23_23") (pintype "bidirectional"))
    )
    (net (code "39") (name "RESE") (class "Default")
      (node (ref "J1") (pin "3") (pinfunction "3_3") (pintype "bidirectional"))
      (node (ref "Q3") (pin "2") (pinfunction "S_2") (pintype "bidirectional"))
      (node (ref "R3") (pin "2") (pinfunction "2_2") (pintype "passive"))
    )
    (net (code "40") (name "RESE'") (class "Default")
      (node (ref "R2") (pin "2") (pinfunction "2_2") (pintype "passive"))
      (node (ref "R3") (pin "1") (pinfunction "1_1") (pintype "passive"))
      (node (ref "SJ1") (pin "2") (pinfunction "2_2") (pintype "passive"))
    )
    (net (code "41") (name "RESET") (class "Default")
      (node (ref "C5") (pin "1") (pinfunction "1_1") (pintype "passive"))
      (node (ref "IC1") (pin "1") (pinfunction "VOUT_1") (pintype "bidirectional"))
      (node (ref "RESET_BUTTON") (pin "3") (pinfunction "3_3") (pintype "passive"))
      (node (ref "RESET_BUTTON") (pin "4") (pinfunction "4_4") (pintype "passive"))
      (node (ref "R_RESET") (pin "2") (pinfunction "2_2") (pintype "passive"))
      (node (ref "U2") (pin "3") (pinfunction "EN_3") (pintype "input"))
    )
    (net (code "42") (name "RTC_RST") (class "Default")
      (node (ref "U2") (pin "16") (pinfunction "IO18_16") (pintype "bidirectional"))
      (node (ref "U3") (pin "4") (pinfunction "~{RST}_4") (pintype "input"))
    )
    (net (code "43") (name "RX") (class "Default")
      (node (ref "TP2") (pin "TP") (pinfunction "TP_TP") (pintype "input"))
      (node (ref "U2") (pin "24") (pinfunction "RXD0/GPIO17_24") (pintype "bidirectional"))
    )
    (net (code "44") (name "SCK") (class "Default")
      (node (ref "D10") (pin "1") (pinfunction "1_1") (pintype "passive"))
      (node (ref "J1") (pin "13") (pinfunction "13_13") (pintype "bidirectional"))
      (node (ref "J4") (pin "P5") (pinfunction "CLK_P5") (pintype "bidirectional"))
      (node (ref "R6") (pin "1") (pinfunction "1_1") (pintype "passive"))
      (node (ref "TP8") (pin "TP") (pinfunction "TP_TP") (pintype "input"))
      (node (ref "U1") (pin "6") (pinfunction "CLK_6") (pintype "input"))
      (node (ref "U2") (pin "6") (pinfunction "IO6_6") (pintype "bidirectional"))
    )
    (net (code "45") (name "SCL") (class "Default")
      (node (ref "J3") (pin "4") (pinfunction "4_4") (pintype "passive"))
      (node (ref "R2-PINH") (pin "1") (pinfunction "1_1") (pintype "passive"))
      (node (ref "SENSOR2") (pin "4") (pinfunction "SCK_4") (pintype "input"))
      (node (ref "U2") (pin "20") (pinfunction "IO22_20") (pintype "bidirectional"))
      (node (ref "U3") (pin "16") (pinfunction "SCL_16") (pintype "input"))
      (node (ref "U4") (pin "7") (pinfunction "SCL_7") (pintype "input"))
    )
    (net (code "46") (name "SDA") (class "Default")
      (node (ref "J3") (pin "3") (pinfunction "3_3") (pintype "passive"))
      (node (ref "R1-PINH") (pin "1") (pinfunction "1_1") (pintype "passive"))
      (node (ref "SENSOR2") (pin "3") (pinfunction "SDI_3") (pintype "bidirectional"))
      (node (ref "U2") (pin "19") (pinfunction "IO21_19") (pintype "bidirectional"))
      (node (ref "U3") (pin "15") (pinfunction "SDA_15") (pintype "bidirectional"))
      (node (ref "U4") (pin "8") (pinfunction "SDA_8") (pintype "bidirectional"))
    )
    (net (code "47") (name "SRC") (class "Default")
      (node (ref "C4") (pin "2") (pinfunction "2_2") (pintype "passive"))
      (node (ref "D5") (pin "2") (pinfunction "A_2") (pintype "bidirectional"))
      (node (ref "L1") (pin "1") (pinfunction "1_1") (pintype "passive"))
      (node (ref "Q3") (pin "3") (pinfunction "D_3") (pintype "bidirectional"))
    )
    (net (code "48") (name "SS_SD") (class "Default")
      (node (ref "D8") (pin "1") (pinfunction "1_1") (pintype "passive"))
      (node (ref "J4") (pin "P2") (pinfunction "CD/DAT3_P2") (pintype "bidirectional"))
      (node (ref "R10") (pin "1") (pinfunction "1_1") (pintype "passive"))
      (node (ref "U2") (pin "4") (pinfunction "IO4_4") (pintype "bidirectional"))
    )
    (net (code "49") (name "TX") (class "Default")
      (node (ref "TP1") (pin "TP") (pinfunction "TP_TP") (pintype "input"))
      (node (ref "U2") (pin "25") (pinfunction "TXD0/GPIO16_25") (pintype "bidirectional"))
    )
    (net (code "50") (name "USB_D+") (class "Default")
      (node (ref "D1") (pin "2") (pinfunction "I/O1_1_2") (pintype "bidirectional"))
      (node (ref "U2") (pin "14") (pinfunction "IO13_14") (pintype "bidirectional"))
    )
    (net (code "51") (name "USB_D-") (class "Default")
      (node (ref "D1") (pin "4") (pinfunction "I/O2_1_4") (pintype "bidirectional"))
      (node (ref "U2") (pin "13") (pinfunction "IO12_13") (pintype "bidirectional"))
    )
    (net (code "52") (name "VBAT") (class "Default")
      (node (ref "C1_BAT4") (pin "1") (pinfunction "1_1") (pintype "passive"))
      (node (ref "MCP73831") (pin "3") (pinfunction "VBAT_3") (pintype "power_in"))
      (node (ref "Q1") (pin "3") (pinfunction "D_3") (pintype "bidirectional"))
      (node (ref "TP3") (pin "TP") (pinfunction "TP_TP") (pintype "input"))
      (node (ref "U4") (pin "2") (pinfunction "CELL_2") (pintype "power_in"))
      (node (ref "U4") (pin "3") (pinfunction "VDD_3") (pintype "power_in"))
    )
    (net (code "53") (name "VBUS") (class "Default")
      (node (ref "C1_BAT") (pin "1") (pinfunction "1_1") (pintype "passive"))
      (node (ref "C4_USB") (pin "1") (pinfunction "1_1") (pintype "passive"))
      (node (ref "C5_USB") (pin "1") (pinfunction "1_1") (pintype "passive"))
      (node (ref "CHG_LED") (pin "A") (pinfunction "A_A") (pintype "passive"))
      (node (ref "D1") (pin "5") (pinfunction "VBUS_5") (pintype "bidirectional"))
      (node (ref "D2") (pin "2") (pinfunction "ANODE_2") (pintype "bidirectional"))
      (node (ref "MCP73831") (pin "4") (pinfunction "VIN_4") (pintype "power_in"))
      (node (ref "PFMF.050.1") (pin "2") (pinfunction "2_2") (pintype "passive"))
      (node (ref "Q1") (pin "1") (pinfunction "G_1") (pintype "bidirectional"))
      (node (ref "R1_PWRUSB") (pin "2") (pinfunction "2_2") (pintype "passive"))
      (node (ref "TP14") (pin "TP") (pinfunction "TP_TP") (pintype "input"))
    )
    (net (code "54") (name "VRTC") (class "Default")
      (node (ref "C10_SUPERCAP") (pin "1") (pinfunction "1_1") (pintype "passive"))
      (node (ref "C8") (pin "1") (pinfunction "1_1") (pintype "passive"))
      (node (ref "R_CAPACITOR") (pin "2") (pinfunction "2_2") (pintype "passive"))
      (node (ref "U3") (pin "14") (pinfunction "VBAT_14") (pintype "power_in"))
    )
    (net (code "55") (name "VUSB") (class "Default")
      (node (ref "J2") (pin "A4") (pinfunction "A4_A4") (pintype "bidirectional"))
      (node (ref "J2") (pin "A9") (pinfunction "A9_A9") (pintype "bidirectional"))
      (node (ref "J2") (pin "B4") (pinfunction "B4_B4") (pintype "bidirectional"))
      (node (ref "J2") (pin "B9") (pinfunction "B9_B9") (pintype "bidirectional"))
      (node (ref "PFMF.050.1") (pin "1") (pinfunction "1_1") (pintype "passive"))
    )
    (net (code "56") (name "unconnected-(IC1-NC-Pad4)") (class "Default")
      (node (ref "IC1") (pin "4") (pinfunction "NC_4") (pintype "no_connect"))
    )
    (net (code "57") (name "unconnected-(IC4-NC-Pad4)") (class "Default")
      (node (ref "IC4") (pin "4") (pinfunction "NC_4") (pintype "no_connect"))
    )
    (net (code "58") (name "unconnected-(J1-Pad1)") (class "Default")
      (node (ref "J1") (pin "1") (pinfunction "1_1") (pintype "bidirectional"))
    )
    (net (code "59") (name "unconnected-(J1-Pad6)") (class "Default")
      (node (ref "J1") (pin "6") (pinfunction "6_6") (pintype "bidirectional"))
    )
    (net (code "60") (name "unconnected-(J1-Pad7)") (class "Default")
      (node (ref "J1") (pin "7") (pinfunction "7_7") (pintype "bidirectional"))
    )
    (net (code "61") (name "unconnected-(J2-PadA8)") (class "Default")
      (node (ref "J2") (pin "A8") (pinfunction "A8_A8") (pintype "bidirectional"))
    )
    (net (code "62") (name "unconnected-(J2-PadB8)") (class "Default")
      (node (ref "J2") (pin "B8") (pinfunction "B8_B8") (pintype "bidirectional"))
    )
    (net (code "63") (name "unconnected-(J4-DAT1-PadP8)") (class "Default")
      (node (ref "J4") (pin "P8") (pinfunction "DAT1_P8") (pintype "bidirectional"))
    )
    (net (code "64") (name "unconnected-(J4-DAT2-PadP1)") (class "Default")
      (node (ref "J4") (pin "P1") (pinfunction "DAT2_P1") (pintype "bidirectional"))
    )
    (net (code "65") (name "unconnected-(J4-DETECTION_1-PadS1)") (class "Default")
      (node (ref "J4") (pin "S1") (pinfunction "DETECTION_1_S1") (pintype "bidirectional"))
    )
    (net (code "66") (name "unconnected-(J4-DETECTION_2-PadS2)") (class "Default")
      (node (ref "J4") (pin "S2") (pinfunction "DETECTION_2_S2") (pintype "bidirectional"))
    )
    (net (code "67") (name "unconnected-(U2-NC-Pad22)") (class "Default")
      (node (ref "U2") (pin "22") (pinfunction "NC_22") (pintype "no_connect"))
    )
    (net (code "68") (name "unconnected-(U4-~{ALERT}-Pad5)") (class "Default")
      (node (ref "U4") (pin "5") (pinfunction "~{ALERT}_5") (pintype "output"))
    )
  )
)
